# 10_1_2021-05-31.net
KiCad netlist of a schematic drawn in EasyEDA
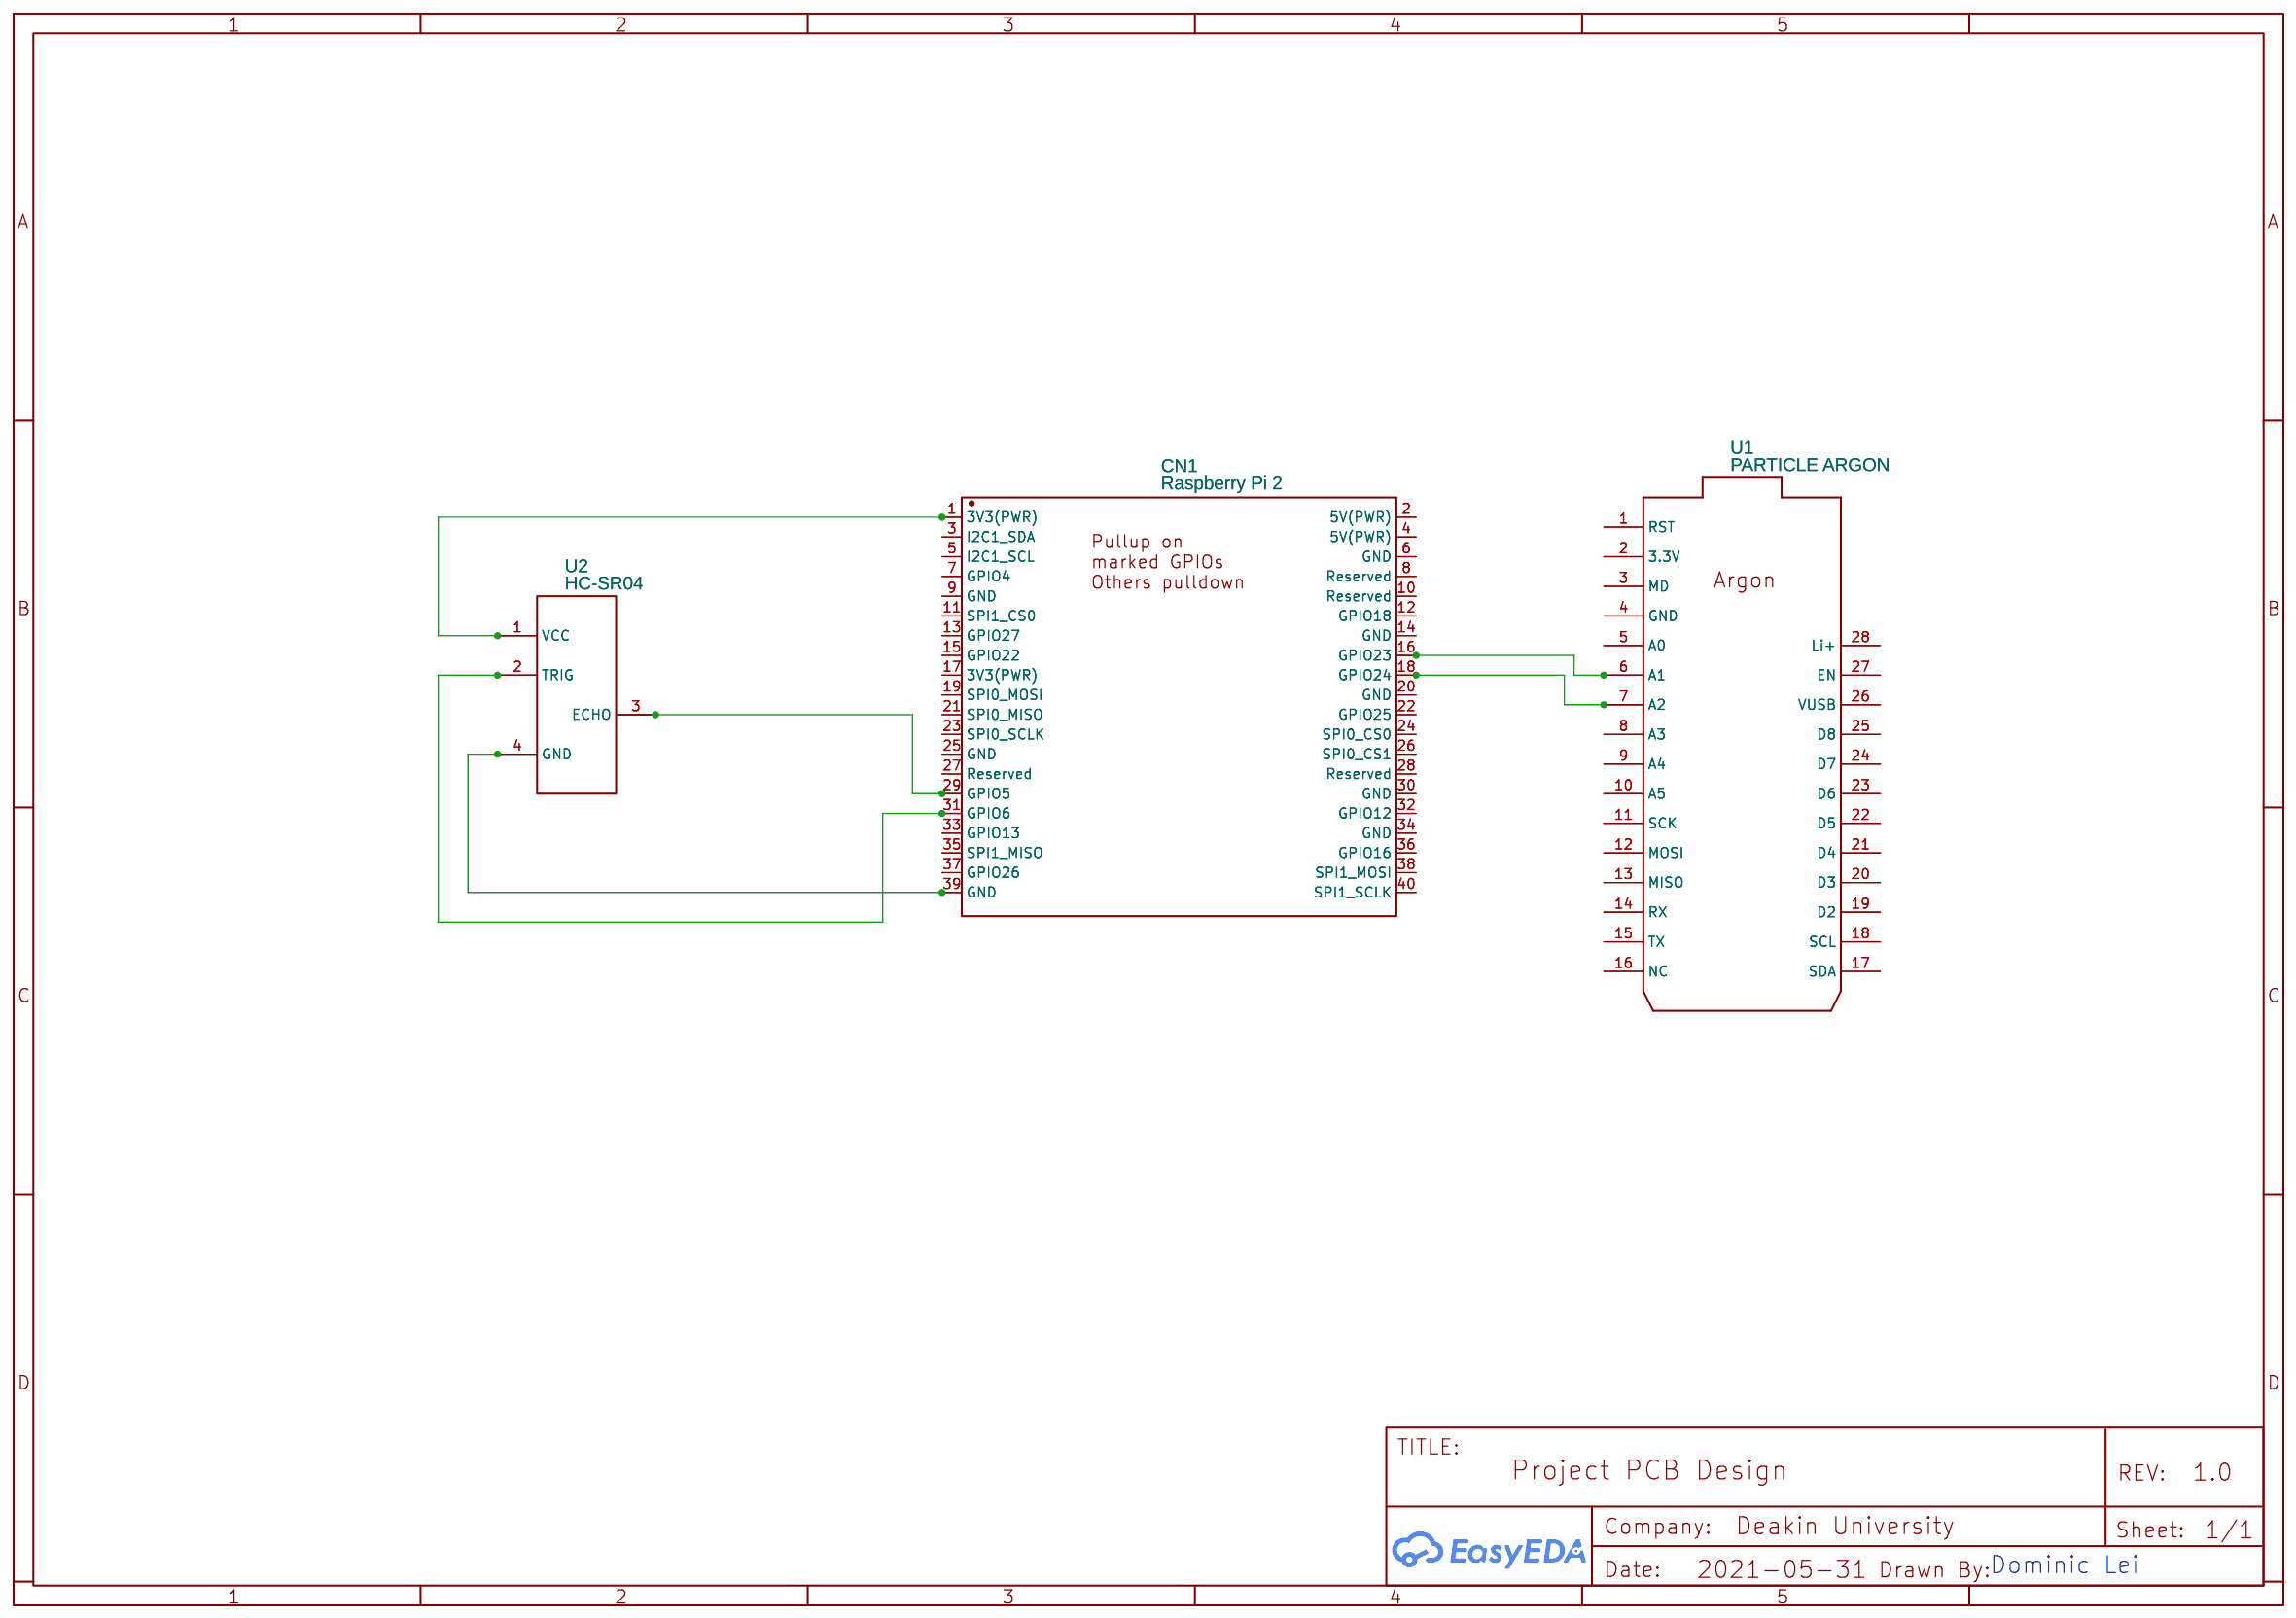
[diagram p0: schematic sheet]

(export (version "E")
  (design (tool "Eeschema 10.0.6"))
  (components
    (comp (ref "CN1") (value "Raspberry Pi 2") (libsource (lib "") (part "Raspberry Pi 2")))
    (comp (ref "U1")
      (value "PARTICLE ARGON")
      (fields (field (name "BOM_Manufacturer Part") "Particle Argon"))
      (libsource (lib "") (part "PARTICLE ARGON"))
    )
    (comp (ref "U2") (value "HC-SR04") (libsource (lib "") (part "HC-SR04")))
  )
  (nets
    (net (code "1") (name "Net-(CN1-GPIO5)") (class "Default")
      (node (ref "CN1") (pin "29") (pinfunction "GPIO5_29") (pintype "bidirectional"))
      (node (ref "U2") (pin "3") (pinfunction "ECHO_3") (pintype "unspecified"))
    )
    (net (code "2") (name "Net-(CN1-GPIO6)") (class "Default")
      (node (ref "CN1") (pin "31") (pinfunction "GPIO6_31") (pintype "bidirectional"))
      (node (ref "U2") (pin "2") (pinfunction "TRIG_2") (pintype "unspecified"))
    )
    (net (code "3") (name "Net-(CN1-GPIO23)") (class "Default")
      (node (ref "CN1") (pin "16") (pinfunction "GPIO23_16") (pintype "bidirectional"))
      (node (ref "U1") (pin "6") (pinfunction "A1_6") (pintype "unspecified"))
    )
    (net (code "4") (name "Net-(CN1-GPIO24)") (class "Default")
      (node (ref "CN1") (pin "18") (pinfunction "GPIO24_18") (pintype "bidirectional"))
      (node (ref "U1") (pin "7") (pinfunction "A2_7") (pintype "unspecified"))
    )
    (net (code "5") (name "Net-(U2-GND)") (class "Default")
      (node (ref "CN1") (pin "39") (pinfunction "GND_39") (pintype "passive"))
      (node (ref "U2") (pin "4") (pinfunction "GND_4") (pintype "unspecified"))
    )
    (net (code "6") (name "Net-(U2-VCC)") (class "Default")
      (node (ref "CN1") (pin "1") (pinfunction "3V3(PWR)_1") (pintype "passive"))
      (node (ref "U2") (pin "1") (pinfunction "VCC_1") (pintype "unspecified"))
    )
    (net (code "7") (name "unconnected-(CN1-3V3(PWR)-Pad17)") (class "Default")
      (node (ref "CN1") (pin "17") (pinfunction "3V3(PWR)_17") (pintype "passive"))
    )
    (net (code "8") (name "unconnected-(CN1-5V(PWR)-Pad2)") (class "Default")
      (node (ref "CN1") (pin "2") (pinfunction "5V(PWR)_2") (pintype "passive"))
    )
    (net (code "9") (name "unconnected-(CN1-5V(PWR)-Pad4)") (class "Default")
      (node (ref "CN1") (pin "4") (pinfunction "5V(PWR)_4") (pintype "passive"))
    )
    (net (code "10") (name "unconnected-(CN1-GND-Pad6)") (class "Default")
      (node (ref "CN1") (pin "6") (pinfunction "GND_6") (pintype "passive"))
    )
    (net (code "11") (name "unconnected-(CN1-GND-Pad9)") (class "Default")
      (node (ref "CN1") (pin "9") (pinfunction "GND_9") (pintype "passive"))
    )
    (net (code "12") (name "unconnected-(CN1-GND-Pad14)") (class "Default")
      (node (ref "CN1") (pin "14") (pinfunction "GND_14") (pintype "passive"))
    )
    (net (code "13") (name "unconnected-(CN1-GND-Pad20)") (class "Default")
      (node (ref "CN1") (pin "20") (pinfunction "GND_20") (pintype "passive"))
    )
    (net (code "14") (name "unconnected-(CN1-GND-Pad25)") (class "Default")
      (node (ref "CN1") (pin "25") (pinfunction "GND_25") (pintype "passive"))
    )
    (net (code "15") (name "unconnected-(CN1-GND-Pad30)") (class "Default")
      (node (ref "CN1") (pin "30") (pinfunction "GND_30") (pintype "passive"))
    )
    (net (code "16") (name "unconnected-(CN1-GND-Pad34)") (class "Default")
      (node (ref "CN1") (pin "34") (pinfunction "GND_34") (pintype "passive"))
    )
    (net (code "17") (name "unconnected-(CN1-GPIO4-Pad7)") (class "Default")
      (node (ref "CN1") (pin "7") (pinfunction "GPIO4_7") (pintype "bidirectional"))
    )
    (net (code "18") (name "unconnected-(CN1-GPIO12-Pad32)") (class "Default")
      (node (ref "CN1") (pin "32") (pinfunction "GPIO12_32") (pintype "bidirectional"))
    )
    (net (code "19") (name "unconnected-(CN1-GPIO13-Pad33)") (class "Default")
      (node (ref "CN1") (pin "33") (pinfunction "GPIO13_33") (pintype "bidirectional"))
    )
    (net (code "20") (name "unconnected-(CN1-GPIO16-Pad36)") (class "Default")
      (node (ref "CN1") (pin "36") (pinfunction "GPIO16_36") (pintype "bidirectional"))
    )
    (net (code "21") (name "unconnected-(CN1-GPIO18-Pad12)") (class "Default")
      (node (ref "CN1") (pin "12") (pinfunction "GPIO18_12") (pintype "bidirectional"))
    )
    (net (code "22") (name "unconnected-(CN1-GPIO22-Pad15)") (class "Default")
      (node (ref "CN1") (pin "15") (pinfunction "GPIO22_15") (pintype "output"))
    )
    (net (code "23") (name "unconnected-(CN1-GPIO25-Pad22)") (class "Default")
      (node (ref "CN1") (pin "22") (pinfunction "GPIO25_22") (pintype "bidirectional"))
    )
    (net (code "24") (name "unconnected-(CN1-GPIO26-Pad37)") (class "Default")
      (node (ref "CN1") (pin "37") (pinfunction "GPIO26_37") (pintype "bidirectional"))
    )
    (net (code "25") (name "unconnected-(CN1-GPIO27-Pad13)") (class "Default")
      (node (ref "CN1") (pin "13") (pinfunction "GPIO27_13") (pintype "bidirectional"))
    )
    (net (code "26") (name "unconnected-(CN1-I2C1_SCL-Pad5)") (class "Default")
      (node (ref "CN1") (pin "5") (pinfunction "I2C1_SCL_5") (pintype "bidirectional"))
    )
    (net (code "27") (name "unconnected-(CN1-I2C1_SDA-Pad3)") (class "Default")
      (node (ref "CN1") (pin "3") (pinfunction "I2C1_SDA_3") (pintype "bidirectional"))
    )
    (net (code "28") (name "unconnected-(CN1-Reserved-Pad8)") (class "Default")
      (node (ref "CN1") (pin "8") (pinfunction "Reserved_8") (pintype "passive"))
    )
    (net (code "29") (name "unconnected-(CN1-Reserved-Pad10)") (class "Default")
      (node (ref "CN1") (pin "10") (pinfunction "Reserved_10") (pintype "bidirectional"))
    )
    (net (code "30") (name "unconnected-(CN1-Reserved-Pad27)") (class "Default")
      (node (ref "CN1") (pin "27") (pinfunction "Reserved_27") (pintype "unspecified"))
    )
    (net (code "31") (name "unconnected-(CN1-Reserved-Pad28)") (class "Default")
      (node (ref "CN1") (pin "28") (pinfunction "Reserved_28") (pintype "unspecified"))
    )
    (net (code "32") (name "unconnected-(CN1-SPI0_CS0-Pad24)") (class "Default")
      (node (ref "CN1") (pin "24") (pinfunction "SPI0_CS0_24") (pintype "bidirectional"))
    )
    (net (code "33") (name "unconnected-(CN1-SPI0_CS1-Pad26)") (class "Default")
      (node (ref "CN1") (pin "26") (pinfunction "SPI0_CS1_26") (pintype "bidirectional"))
    )
    (net (code "34") (name "unconnected-(CN1-SPI0_MISO-Pad21)") (class "Default")
      (node (ref "CN1") (pin "21") (pinfunction "SPI0_MISO_21") (pintype "bidirectional"))
    )
    (net (code "35") (name "unconnected-(CN1-SPI0_MOSI-Pad19)") (class "Default")
      (node (ref "CN1") (pin "19") (pinfunction "SPI0_MOSI_19") (pintype "bidirectional"))
    )
    (net (code "36") (name "unconnected-(CN1-SPI0_SCLK-Pad23)") (class "Default")
      (node (ref "CN1") (pin "23") (pinfunction "SPI0_SCLK_23") (pintype "bidirectional"))
    )
    (net (code "37") (name "unconnected-(CN1-SPI1_CS0-Pad11)") (class "Default")
      (node (ref "CN1") (pin "11") (pinfunction "SPI1_CS0_11") (pintype "bidirectional"))
    )
    (net (code "38") (name "unconnected-(CN1-SPI1_MISO-Pad35)") (class "Default")
      (node (ref "CN1") (pin "35") (pinfunction "SPI1_MISO_35") (pintype "bidirectional"))
    )
    (net (code "39") (name "unconnected-(CN1-SPI1_MOSI-Pad38)") (class "Default")
      (node (ref "CN1") (pin "38") (pinfunction "SPI1_MOSI_38") (pintype "bidirectional"))
    )
    (net (code "40") (name "unconnected-(CN1-SPI1_SCLK-Pad40)") (class "Default")
      (node (ref "CN1") (pin "40") (pinfunction "SPI1_SCLK_40") (pintype "bidirectional"))
    )
    (net (code "41") (name "unconnected-(U1-3.3V-Pad2)") (class "Default")
      (node (ref "U1") (pin "2") (pinfunction "3.3V_2") (pintype "unspecified"))
    )
    (net (code "42") (name "unconnected-(U1-A0-Pad5)") (class "Default")
      (node (ref "U1") (pin "5") (pinfunction "A0_5") (pintype "unspecified"))
    )
    (net (code "43") (name "unconnected-(U1-A3-Pad8)") (class "Default")
      (node (ref "U1") (pin "8") (pinfunction "A3_8") (pintype "unspecified"))
    )
    (net (code "44") (name "unconnected-(U1-A4-Pad9)") (class "Default")
      (node (ref "U1") (pin "9") (pinfunction "A4_9") (pintype "unspecified"))
    )
    (net (code "45") (name "unconnected-(U1-A5-Pad10)") (class "Default")
      (node (ref "U1") (pin "10") (pinfunction "A5_10") (pintype "unspecified"))
    )
    (net (code "46") (name "unconnected-(U1-D2-Pad19)") (class "Default")
      (node (ref "U1") (pin "19") (pinfunction "D2_19") (pintype "unspecified"))
    )
    (net (code "47") (name "unconnected-(U1-D3-Pad20)") (class "Default")
      (node (ref "U1") (pin "20") (pinfunction "D3_20") (pintype "unspecified"))
    )
    (net (code "48") (name "unconnected-(U1-D4-Pad21)") (class "Default")
      (node (ref "U1") (pin "21") (pinfunction "D4_21") (pintype "unspecified"))
    )
    (net (code "49") (name "unconnected-(U1-D5-Pad22)") (class "Default")
      (node (ref "U1") (pin "22") (pinfunction "D5_22") (pintype "unspecified"))
    )
    (net (code "50") (name "unconnected-(U1-D6-Pad23)") (class "Default")
      (node (ref "U1") (pin "23") (pinfunction "D6_23") (pintype "unspecified"))
    )
    (net (code "51") (name "unconnected-(U1-D7-Pad24)") (class "Default")
      (node (ref "U1") (pin "24") (pinfunction "D7_24") (pintype "unspecified"))
    )
    (net (code "52") (name "unconnected-(U1-D8-Pad25)") (class "Default")
      (node (ref "U1") (pin "25") (pinfunction "D8_25") (pintype "unspecified"))
    )
    (net (code "53") (name "unconnected-(U1-EN-Pad27)") (class "Default")
      (node (ref "U1") (pin "27") (pinfunction "EN_27") (pintype "unspecified"))
    )
    (net (code "54") (name "unconnected-(U1-GND-Pad4)") (class "Default")
      (node (ref "U1") (pin "4") (pinfunction "GND_4") (pintype "unspecified"))
    )
    (net (code "55") (name "unconnected-(U1-Li+-Pad28)") (class "Default")
      (node (ref "U1") (pin "28") (pinfunction "Li+_28") (pintype "unspecified"))
    )
    (net (code "56") (name "unconnected-(U1-MD-Pad3)") (class "Default")
      (node (ref "U1") (pin "3") (pinfunction "MD_3") (pintype "unspecified"))
    )
    (net (code "57") (name "unconnected-(U1-MISO-Pad13)") (class "Default")
      (node (ref "U1") (pin "13") (pinfunction "MISO_13") (pintype "unspecified"))
    )
    (net (code "58") (name "unconnected-(U1-MOSI-Pad12)") (class "Default")
      (node (ref "U1") (pin "12") (pinfunction "MOSI_12") (pintype "unspecified"))
    )
    (net (code "59") (name "unconnected-(U1-NC-Pad16)") (class "Default")
      (node (ref "U1") (pin "16") (pinfunction "NC_16") (pintype "unspecified"))
    )
    (net (code "60") (name "unconnected-(U1-RST-Pad1)") (class "Default")
      (node (ref "U1") (pin "1") (pinfunction "RST_1") (pintype "unspecified"))
    )
    (net (code "61") (name "unconnected-(U1-RX-Pad14)") (class "Default")
      (node (ref "U1") (pin "14") (pinfunction "RX_14") (pintype "unspecified"))
    )
    (net (code "62") (name "unconnected-(U1-SCK-Pad11)") (class "Default")
      (node (ref "U1") (pin "11") (pinfunction "SCK_11") (pintype "unspecified"))
    )
    (net (code "63") (name "unconnected-(U1-SCL-Pad18)") (class "Default")
      (node (ref "U1") (pin "18") (pinfunction "SCL_18") (pintype "unspecified"))
    )
    (net (code "64") (name "unconnected-(U1-SDA-Pad17)") (class "Default")
      (node (ref "U1") (pin "17") (pinfunction "SDA_17") (pintype "unspecified"))
    )
    (net (code "65") (name "unconnected-(U1-TX-Pad15)") (class "Default")
      (node (ref "U1") (pin "15") (pinfunction "TX_15") (pintype "unspecified"))
    )
    (net (code "66") (name "unconnected-(U1-VUSB-Pad26)") (class "Default")
      (node (ref "U1") (pin "26") (pinfunction "VUSB_26") (pintype "unspecified"))
    )
  )
)
